# board_l_ten.net
KiCad netlist of a schematic drawn in EAGLE
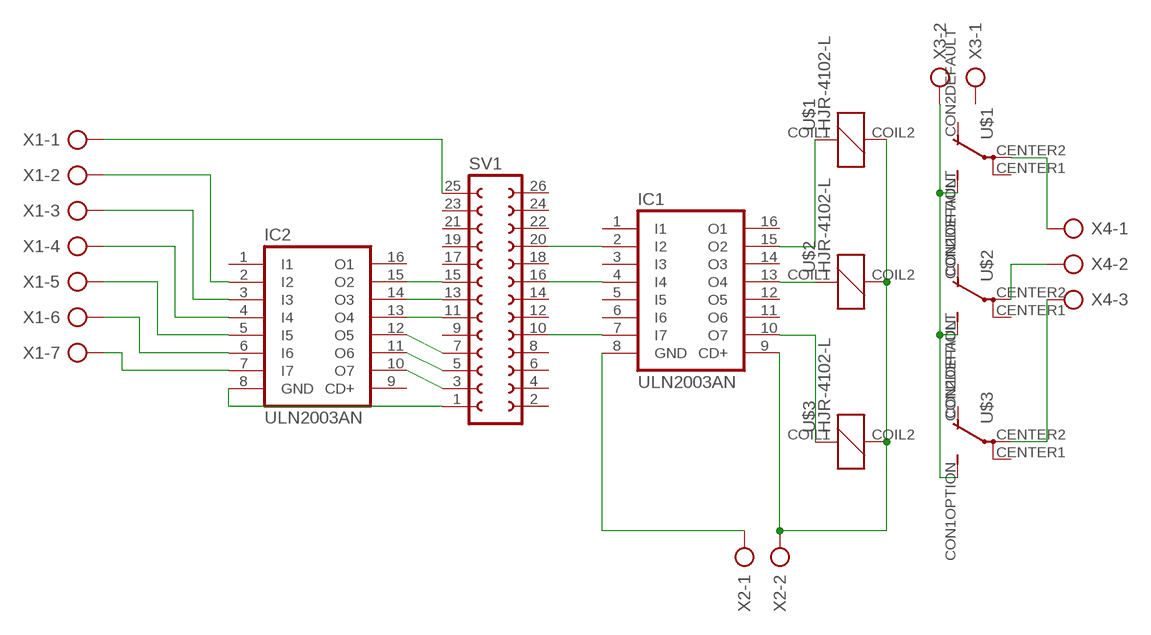
[diagram p0: schematic, sheet 1]

(export (version "E")
  (design (tool "Eeschema 10.0.6"))
  (components
    (comp (ref "IC1")
      (value "ULN2003AN")
      (footprint "eagle-import:DIL16")
      (libsource (lib "eagle-import") (part "ULN2003AN"))
    )
    (comp (ref "IC2")
      (value "ULN2003AN")
      (footprint "eagle-import:DIL16")
      (libsource (lib "eagle-import") (part "ULN2003AN"))
    )
    (comp (ref "SV1")
      (value "FE13-2")
      (footprint "eagle-import:FE13-2")
      (libsource (lib "eagle-import") (part "FE13-2"))
    )
    (comp (ref "U$1")
      (value "HJR-4102-L")
      (footprint "eagle-import:HJR4102")
      (libsource (lib "eagle-import") (part "HJR-4102-L"))
    )
    (comp (ref "U$2")
      (value "HJR-4102-L")
      (footprint "eagle-import:HJR4102")
      (libsource (lib "eagle-import") (part "HJR-4102-L"))
    )
    (comp (ref "U$3")
      (value "HJR-4102-L")
      (footprint "eagle-import:HJR4102")
      (libsource (lib "eagle-import") (part "HJR-4102-L"))
    )
    (comp (ref "X1")
      (value "AK500/7")
      (footprint "eagle-import:AK500_7")
      (libsource (lib "eagle-import") (part "AK500/7"))
    )
    (comp (ref "X2")
      (value "AK500/2")
      (footprint "eagle-import:AK500_2")
      (libsource (lib "eagle-import") (part "AK500/2"))
    )
    (comp (ref "X3")
      (value "AK500/2")
      (footprint "eagle-import:AK500_2")
      (libsource (lib "eagle-import") (part "AK500/2"))
    )
    (comp (ref "X4")
      (value "AK500/3")
      (footprint "eagle-import:AK500_3")
      (libsource (lib "eagle-import") (part "AK500/3"))
    )
  )
  (nets
    (net (code "1") (name "Net-(IC1-CD+)") (class "Default")
      (node (ref "IC1") (pin "9") (pinfunction "CD+_9") (pintype "passive"))
      (node (ref "U$1") (pin "COIL2") (pinfunction "2_COIL2") (pintype "passive"))
      (node (ref "U$2") (pin "COIL2") (pinfunction "2_COIL2") (pintype "passive"))
      (node (ref "U$3") (pin "COIL2") (pinfunction "2_COIL2") (pintype "passive"))
      (node (ref "X2") (pin "2") (pinfunction "KL_2") (pintype "passive"))
    )
    (net (code "2") (name "Net-(IC1-GND)") (class "Default")
      (node (ref "IC1") (pin "8") (pinfunction "GND_8") (pintype "power_in"))
      (node (ref "X2") (pin "1") (pinfunction "KL_1") (pintype "passive"))
    )
    (net (code "3") (name "Net-(IC1-I2)") (class "Default")
      (node (ref "IC1") (pin "2") (pinfunction "I2_2") (pintype "input"))
      (node (ref "SV1") (pin "20") (pinfunction "20_20") (pintype "passive"))
    )
    (net (code "4") (name "Net-(IC1-I4)") (class "Default")
      (node (ref "IC1") (pin "4") (pinfunction "I4_4") (pintype "input"))
      (node (ref "SV1") (pin "16") (pinfunction "16_16") (pintype "passive"))
    )
    (net (code "5") (name "Net-(IC1-I7)") (class "Default")
      (node (ref "IC1") (pin "7") (pinfunction "I7_7") (pintype "input"))
      (node (ref "SV1") (pin "10") (pinfunction "10_10") (pintype "passive"))
    )
    (net (code "6") (name "Net-(IC1-O2)") (class "Default")
      (node (ref "IC1") (pin "15") (pinfunction "O2_15") (pintype "open_collector"))
      (node (ref "U$1") (pin "COIL1") (pinfunction "1_COIL1") (pintype "passive"))
    )
    (net (code "7") (name "Net-(IC1-O4)") (class "Default")
      (node (ref "IC1") (pin "13") (pinfunction "O4_13") (pintype "open_collector"))
      (node (ref "U$2") (pin "COIL1") (pinfunction "1_COIL1") (pintype "passive"))
    )
    (net (code "8") (name "Net-(IC1-O7)") (class "Default")
      (node (ref "IC1") (pin "10") (pinfunction "O7_10") (pintype "open_collector"))
      (node (ref "U$3") (pin "COIL1") (pinfunction "1_COIL1") (pintype "passive"))
    )
    (net (code "9") (name "Net-(IC2-GND)") (class "Default")
      (node (ref "IC2") (pin "8") (pinfunction "GND_8") (pintype "power_in"))
      (node (ref "SV1") (pin "1") (pinfunction "1_1") (pintype "passive"))
    )
    (net (code "10") (name "Net-(IC2-I2)") (class "Default")
      (node (ref "IC2") (pin "2") (pinfunction "I2_2") (pintype "input"))
      (node (ref "X1") (pin "2") (pinfunction "KL_2") (pintype "passive"))
    )
    (net (code "11") (name "Net-(IC2-I3)") (class "Default")
      (node (ref "IC2") (pin "3") (pinfunction "I3_3") (pintype "input"))
      (node (ref "X1") (pin "3") (pinfunction "KL_3") (pintype "passive"))
    )
    (net (code "12") (name "Net-(IC2-I4)") (class "Default")
      (node (ref "IC2") (pin "4") (pinfunction "I4_4") (pintype "input"))
      (node (ref "X1") (pin "4") (pinfunction "KL_4") (pintype "passive"))
    )
    (net (code "13") (name "Net-(IC2-I5)") (class "Default")
      (node (ref "IC2") (pin "5") (pinfunction "I5_5") (pintype "input"))
      (node (ref "X1") (pin "5") (pinfunction "KL_5") (pintype "passive"))
    )
    (net (code "14") (name "Net-(IC2-I6)") (class "Default")
      (node (ref "IC2") (pin "6") (pinfunction "I6_6") (pintype "input"))
      (node (ref "X1") (pin "6") (pinfunction "KL_6") (pintype "passive"))
    )
    (net (code "15") (name "Net-(IC2-I7)") (class "Default")
      (node (ref "IC2") (pin "7") (pinfunction "I7_7") (pintype "input"))
      (node (ref "X1") (pin "7") (pinfunction "KL_7") (pintype "passive"))
    )
    (net (code "16") (name "Net-(IC2-O2)") (class "Default")
      (node (ref "IC2") (pin "15") (pinfunction "O2_15") (pintype "open_collector"))
      (node (ref "SV1") (pin "15") (pinfunction "15_15") (pintype "passive"))
    )
    (net (code "17") (name "Net-(IC2-O3)") (class "Default")
      (node (ref "IC2") (pin "14") (pinfunction "O3_14") (pintype "open_collector"))
      (node (ref "SV1") (pin "13") (pinfunction "13_13") (pintype "passive"))
    )
    (net (code "18") (name "Net-(IC2-O4)") (class "Default")
      (node (ref "IC2") (pin "13") (pinfunction "O4_13") (pintype "open_collector"))
      (node (ref "SV1") (pin "11") (pinfunction "11_11") (pintype "passive"))
    )
    (net (code "19") (name "Net-(IC2-O5)") (class "Default")
      (node (ref "IC2") (pin "12") (pinfunction "O5_12") (pintype "open_collector"))
      (node (ref "SV1") (pin "7") (pinfunction "7_7") (pintype "passive"))
    )
    (net (code "20") (name "Net-(IC2-O6)") (class "Default")
      (node (ref "IC2") (pin "11") (pinfunction "O6_11") (pintype "open_collector"))
      (node (ref "SV1") (pin "5") (pinfunction "5_5") (pintype "passive"))
    )
    (net (code "21") (name "Net-(IC2-O7)") (class "Default")
      (node (ref "IC2") (pin "10") (pinfunction "O7_10") (pintype "open_collector"))
      (node (ref "SV1") (pin "3") (pinfunction "3_3") (pintype "passive"))
    )
    (net (code "22") (name "Net-(U$1B-S)") (class "Default")
      (node (ref "U$1") (pin "CON1OPTION") (pinfunction "S_CON1OPTION") (pintype "passive"))
      (node (ref "U$2") (pin "CON1OPTION") (pinfunction "S_CON1OPTION") (pintype "passive"))
      (node (ref "U$3") (pin "CON1OPTION") (pinfunction "S_CON1OPTION") (pintype "passive"))
      (node (ref "X3") (pin "2") (pinfunction "KL_2") (pintype "passive"))
    )
    (net (code "23") (name "Net-(X1A-KL)") (class "Default")
      (node (ref "SV1") (pin "25") (pinfunction "25_25") (pintype "passive"))
      (node (ref "X1") (pin "1") (pinfunction "KL_1") (pintype "passive"))
    )
    (net (code "24") (name "Net-(X4A-KL)") (class "Default")
      (node (ref "U$1") (pin "CENTER2") (pinfunction "P_CENTER2") (pintype "passive"))
      (node (ref "X4") (pin "1") (pinfunction "KL_1") (pintype "passive"))
    )
    (net (code "25") (name "Net-(X4B-KL)") (class "Default")
      (node (ref "U$2") (pin "CENTER2") (pinfunction "P_CENTER2") (pintype "passive"))
      (node (ref "X4") (pin "2") (pinfunction "KL_2") (pintype "passive"))
    )
    (net (code "26") (name "Net-(X4C-KL)") (class "Default")
      (node (ref "U$3") (pin "CENTER2") (pinfunction "P_CENTER2") (pintype "passive"))
      (node (ref "X4") (pin "3") (pinfunction "KL_3") (pintype "passive"))
    )
    (net (code "27") (name "unconnected-(IC1-I1-Pad1)") (class "Default")
      (node (ref "IC1") (pin "1") (pinfunction "I1_1") (pintype "input"))
    )
    (net (code "28") (name "unconnected-(IC1-I3-Pad3)") (class "Default")
      (node (ref "IC1") (pin "3") (pinfunction "I3_3") (pintype "input"))
    )
    (net (code "29") (name "unconnected-(IC1-I5-Pad5)") (class "Default")
      (node (ref "IC1") (pin "5") (pinfunction "I5_5") (pintype "input"))
    )
    (net (code "30") (name "unconnected-(IC1-I6-Pad6)") (class "Default")
      (node (ref "IC1") (pin "6") (pinfunction "I6_6") (pintype "input"))
    )
    (net (code "31") (name "unconnected-(IC1-O1-Pad16)") (class "Default")
      (node (ref "IC1") (pin "16") (pinfunction "O1_16") (pintype "open_collector"))
    )
    (net (code "32") (name "unconnected-(IC1-O3-Pad14)") (class "Default")
      (node (ref "IC1") (pin "14") (pinfunction "O3_14") (pintype "open_collector"))
    )
    (net (code "33") (name "unconnected-(IC1-O5-Pad12)") (class "Default")
      (node (ref "IC1") (pin "12") (pinfunction "O5_12") (pintype "open_collector"))
    )
    (net (code "34") (name "unconnected-(IC1-O6-Pad11)") (class "Default")
      (node (ref "IC1") (pin "11") (pinfunction "O6_11") (pintype "open_collector"))
    )
    (net (code "35") (name "unconnected-(IC2-CD+-Pad9)") (class "Default")
      (node (ref "IC2") (pin "9") (pinfunction "CD+_9") (pintype "passive"))
    )
    (net (code "36") (name "unconnected-(IC2-I1-Pad1)") (class "Default")
      (node (ref "IC2") (pin "1") (pinfunction "I1_1") (pintype "input"))
    )
    (net (code "37") (name "unconnected-(IC2-O1-Pad16)") (class "Default")
      (node (ref "IC2") (pin "16") (pinfunction "O1_16") (pintype "open_collector"))
    )
    (net (code "38") (name "unconnected-(SV1-Pad2)") (class "Default")
      (node (ref "SV1") (pin "2") (pinfunction "2_2") (pintype "passive"))
    )
    (net (code "39") (name "unconnected-(SV1-Pad4)") (class "Default")
      (node (ref "SV1") (pin "4") (pinfunction "4_4") (pintype "passive"))
    )
    (net (code "40") (name "unconnected-(SV1-Pad6)") (class "Default")
      (node (ref "SV1") (pin "6") (pinfunction "6_6") (pintype "passive"))
    )
    (net (code "41") (name "unconnected-(SV1-Pad8)") (class "Default")
      (node (ref "SV1") (pin "8") (pinfunction "8_8") (pintype "passive"))
    )
    (net (code "42") (name "unconnected-(SV1-Pad9)") (class "Default")
      (node (ref "SV1") (pin "9") (pinfunction "9_9") (pintype "passive"))
    )
    (net (code "43") (name "unconnected-(SV1-Pad12)") (class "Default")
      (node (ref "SV1") (pin "12") (pinfunction "12_12") (pintype "passive"))
    )
    (net (code "44") (name "unconnected-(SV1-Pad14)") (class "Default")
      (node (ref "SV1") (pin "14") (pinfunction "14_14") (pintype "passive"))
    )
    (net (code "45") (name "unconnected-(SV1-Pad17)") (class "Default")
      (node (ref "SV1") (pin "17") (pinfunction "17_17") (pintype "passive"))
    )
    (net (code "46") (name "unconnected-(SV1-Pad18)") (class "Default")
      (node (ref "SV1") (pin "18") (pinfunction "18_18") (pintype "passive"))
    )
    (net (code "47") (name "unconnected-(SV1-Pad19)") (class "Default")
      (node (ref "SV1") (pin "19") (pinfunction "19_19") (pintype "passive"))
    )
    (net (code "48") (name "unconnected-(SV1-Pad21)") (class "Default")
      (node (ref "SV1") (pin "21") (pinfunction "21_21") (pintype "passive"))
    )
    (net (code "49") (name "unconnected-(SV1-Pad22)") (class "Default")
      (node (ref "SV1") (pin "22") (pinfunction "22_22") (pintype "passive"))
    )
    (net (code "50") (name "unconnected-(SV1-Pad23)") (class "Default")
      (node (ref "SV1") (pin "23") (pinfunction "23_23") (pintype "passive"))
    )
    (net (code "51") (name "unconnected-(SV1-Pad24)") (class "Default")
      (node (ref "SV1") (pin "24") (pinfunction "24_24") (pintype "passive"))
    )
    (net (code "52") (name "unconnected-(SV1-Pad26)") (class "Default")
      (node (ref "SV1") (pin "26") (pinfunction "26_26") (pintype "passive"))
    )
    (net (code "53") (name "unconnected-(U$1B-O-PadCON2DEFAULT)") (class "Default")
      (node (ref "U$1") (pin "CON2DEFAULT") (pinfunction "O_CON2DEFAULT") (pintype "passive"))
    )
    (net (code "54") (name "unconnected-(U$1B-P-PadCENTER1)") (class "Default")
      (node (ref "U$1") (pin "CENTER1") (pinfunction "P_CENTER1") (pintype "passive"))
    )
    (net (code "55") (name "unconnected-(U$2B-O-PadCON2DEFAULT)") (class "Default")
      (node (ref "U$2") (pin "CON2DEFAULT") (pinfunction "O_CON2DEFAULT") (pintype "passive"))
    )
    (net (code "56") (name "unconnected-(U$2B-P-PadCENTER1)") (class "Default")
      (node (ref "U$2") (pin "CENTER1") (pinfunction "P_CENTER1") (pintype "passive"))
    )
    (net (code "57") (name "unconnected-(U$3B-O-PadCON2DEFAULT)") (class "Default")
      (node (ref "U$3") (pin "CON2DEFAULT") (pinfunction "O_CON2DEFAULT") (pintype "passive"))
    )
    (net (code "58") (name "unconnected-(U$3B-P-PadCENTER1)") (class "Default")
      (node (ref "U$3") (pin "CENTER1") (pinfunction "P_CENTER1") (pintype "passive"))
    )
    (net (code "59") (name "unconnected-(X3A-KL-Pad1)") (class "Default")
      (node (ref "X3") (pin "1") (pinfunction "KL_1") (pintype "passive"))
    )
  )
)
